# Power_Circuit.net
KiCad netlist of a schematic drawn in Altium Designer
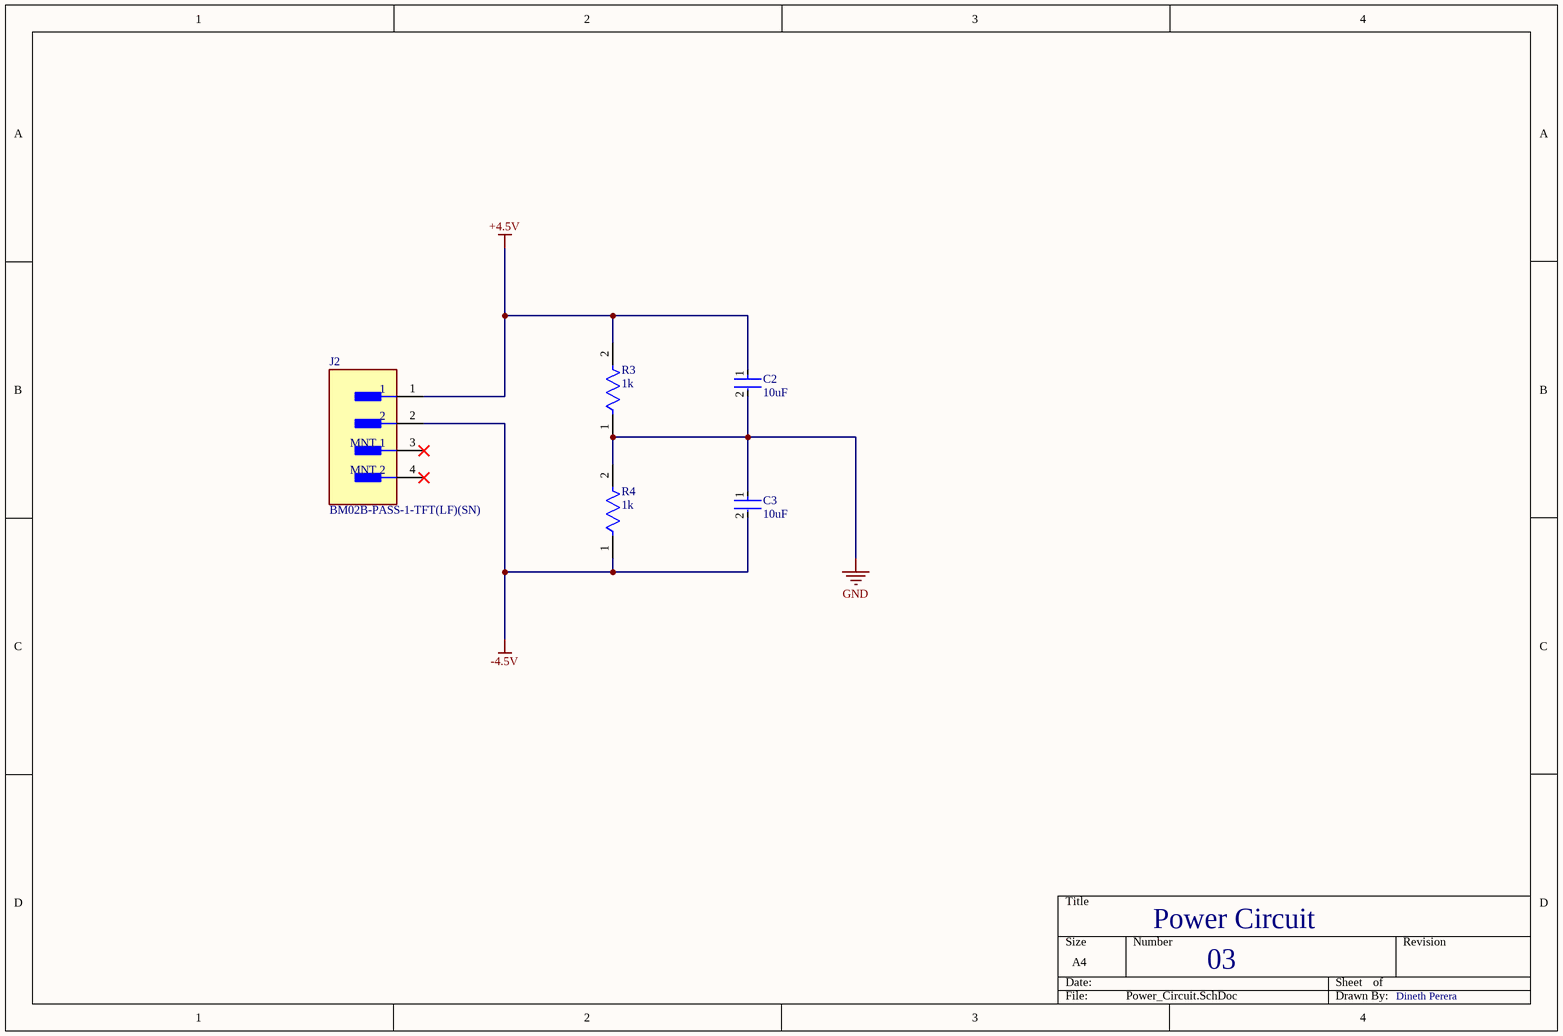
[diagram p0: Power_Circuit.SchDoc]

(export (version "E")
  (design (tool "Eeschema 10.0.6"))
  (components
    (comp (ref "C2")
      (value "10uF")
      (footprint "FP-GRM21B-0_1-IPC_C")
      (description "Chip Multilayer Ceramic Capacitors for General Purpose, 0805, 10uF, X5R, 15%, 10%, 16V")
      (fields (field (name "TOLERANCE") "10%") (field (name "VOLTAGE") "16V"))
      (libsource (lib "Altium Content Vault") (part "b4654b650e69147ec39a6b967a45e02"))
    )
    (comp (ref "C3")
      (value "10uF")
      (footprint "FP-GRM21B-0_1-IPC_C")
      (description "Chip Multilayer Ceramic Capacitors for General Purpose, 0805, 10uF, X5R, 15%, 10%, 16V")
      (fields (field (name "TOLERANCE") "10%") (field (name "VOLTAGE") "16V"))
      (libsource (lib "Altium Content Vault") (part "b4654b650e69147ec39a6b967a45e02"))
    )
    (comp (ref "J2")
      (value "BM02B-PASS-1-TFT(LF)(SN)")
      (footprint "FP-BM02B-PASS-1-TFT_LF_S-MFG")
      (description "CONN HEADER SMD 2POS 2MM")
      (libsource (lib "Altium Content Vault") (part "6ebc6fc72a9fd5a6899c7600f385cff"))
    )
    (comp (ref "R3")
      (value "1k")
      (footprint "FP-ERA6A-IPC_C")
      (description "RES 1K OHM 0.1% 1/8W 0805")
      (fields (field (name "TOLERANCE") "0.1%"))
      (libsource (lib "Altium Content Vault") (part "1029c3af85768c4190bb7ad29bc67b5"))
    )
    (comp (ref "R4")
      (value "1k")
      (footprint "FP-ERA6A-IPC_C")
      (description "RES 1K OHM 0.1% 1/8W 0805")
      (fields (field (name "TOLERANCE") "0.1%"))
      (libsource (lib "Altium Content Vault") (part "1029c3af85768c4190bb7ad29bc67b5"))
    )
  )
  (nets
    (net (code "1") (name "+4.5V") (class "Default")
      (node (ref "C2") (pin "1") (pinfunction "1_1") (pintype "passive"))
      (node (ref "J2") (pin "1") (pinfunction "1_1") (pintype "passive"))
      (node (ref "R3") (pin "2") (pinfunction "2_2") (pintype "passive"))
    )
    (net (code "2") (name "-4.5V") (class "Default")
      (node (ref "C3") (pin "2") (pinfunction "2_2") (pintype "passive"))
      (node (ref "J2") (pin "2") (pinfunction "2_2") (pintype "passive"))
      (node (ref "R4") (pin "1") (pinfunction "1_1") (pintype "passive"))
    )
    (net (code "3") (name "GND") (class "Default")
      (node (ref "C2") (pin "2") (pinfunction "2_2") (pintype "passive"))
      (node (ref "C3") (pin "1") (pinfunction "1_1") (pintype "passive"))
      (node (ref "R3") (pin "1") (pinfunction "1_1") (pintype "passive"))
      (node (ref "R4") (pin "2") (pinfunction "2_2") (pintype "passive"))
    )
    (net (code "4") (name "unconnected-(J2-MNT_1-Pad3)") (class "Default")
      (node (ref "J2") (pin "3") (pinfunction "MNT_1_3") (pintype "passive+no_connect"))
    )
    (net (code "5") (name "unconnected-(J2-MNT_2-Pad4)") (class "Default")
      (node (ref "J2") (pin "4") (pinfunction "MNT_2_4") (pintype "passive+no_connect"))
    )
  )
)
